# Part29.net
KiCad netlist of a schematic drawn in Altium Designer
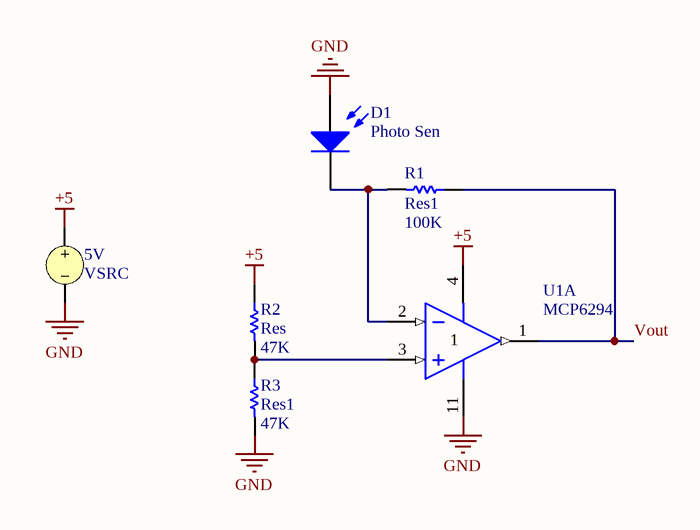
[diagram p0: Part29.SchDoc]

(export (version "E")
  (design (tool "Eeschema 10.0.6"))
  (components
    (comp (ref "5V")
      (value "VSRC")
      (description "Voltage Source")
      (fields (field (name "PUBLISHER") "Altium Limited"))
      (libsource (lib "Simulation Sources") (part "VSRC"))
    )
    (comp (ref "D1")
      (value "Photo Sen")
      (footprint "PIN2")
      (description "Photosensitive Diode")
      (fields (field (name "MANUFACTURER") "Generic Components"))
      (libsource (lib "ME218_BaseLib") (part "Photo Sen"))
    )
    (comp (ref "R1")
      (value "Res1")
      (footprint "AXIAL-0.3")
      (description "Resistor")
      (fields
        (field (name "MANUFACTURER") "Generic Components")
        (field (name "ALTIUM_VALUE") "100K")
        (field (name "PUBLISHER") "Altium Hobart Technology Centre")
      )
      (libsource (lib "ME218_BaseLib") (part "Res1"))
    )
    (comp (ref "R2")
      (value "Res")
      (footprint "AXIAL-0.3")
      (description "Resistor")
      (fields
        (field (name "MANUFACTURER") "Generic Components")
        (field (name "ALTIUM_VALUE") "47K")
        (field (name "PUBLISHER") "Altium Hobart Technology Centre")
      )
      (libsource (lib "ME218_BaseLib") (part "Res1"))
    )
    (comp (ref "R3")
      (value "Res1")
      (footprint "AXIAL-0.3")
      (description "Resistor")
      (fields
        (field (name "MANUFACTURER") "Generic Components")
        (field (name "ALTIUM_VALUE") "47K")
        (field (name "PUBLISHER") "Altium Hobart Technology Centre")
      )
      (libsource (lib "ME218_BaseLib") (part "Res1"))
    )
    (comp (ref "U1")
      (value "MCP6294")
      (footprint "DIP-14")
      (description "Low-Power Quad Operational Amplifier")
      (fields
        (field (name "MANUFACTURER") "National Semiconductor")
        (field (name "PUBLISHER") "Altium Hobart Technology Centre")
      )
      (libsource (lib "ME218_BaseLib") (part "LM324AJ"))
    )
  )
  (nets
    (net (code "1") (name "+5") (class "Default")
      (node (ref "5V") (pin "1") (pinfunction "1_1") (pintype "passive"))
      (node (ref "R2") (pin "1") (pinfunction "1_1") (pintype "passive"))
      (node (ref "U1") (pin "4") (pinfunction "V+_4") (pintype "power_in"))
    )
    (net (code "2") (name "/Vout") (class "Default")
      (node (ref "R1") (pin "1") (pinfunction "1_1") (pintype "passive"))
      (node (ref "U1") (pin "1") (pinfunction "OUT_1") (pintype "output"))
    )
    (net (code "3") (name "GND") (class "Default")
      (node (ref "5V") (pin "2") (pinfunction "2_2") (pintype "passive"))
      (node (ref "D1") (pin "1") (pinfunction "A_1") (pintype "passive"))
      (node (ref "R3") (pin "2") (pinfunction "2_2") (pintype "passive"))
      (node (ref "U1") (pin "11") (pinfunction "GND_11") (pintype "power_in"))
    )
    (net (code "4") (name "Net-(D1-K)") (class "Default")
      (node (ref "D1") (pin "2") (pinfunction "K_2") (pintype "passive"))
      (node (ref "R1") (pin "2") (pinfunction "2_2") (pintype "passive"))
      (node (ref "U1") (pin "2") (pinfunction "IN-_2") (pintype "input"))
    )
    (net (code "5") (name "Net-(U1A-IN+)") (class "Default")
      (node (ref "R2") (pin "2") (pinfunction "2_2") (pintype "passive"))
      (node (ref "R3") (pin "1") (pinfunction "1_1") (pintype "passive"))
      (node (ref "U1") (pin "3") (pinfunction "IN+_3") (pintype "input"))
    )
  )
)
